# JR_main.net
KiCad netlist of a schematic drawn in Altium Designer
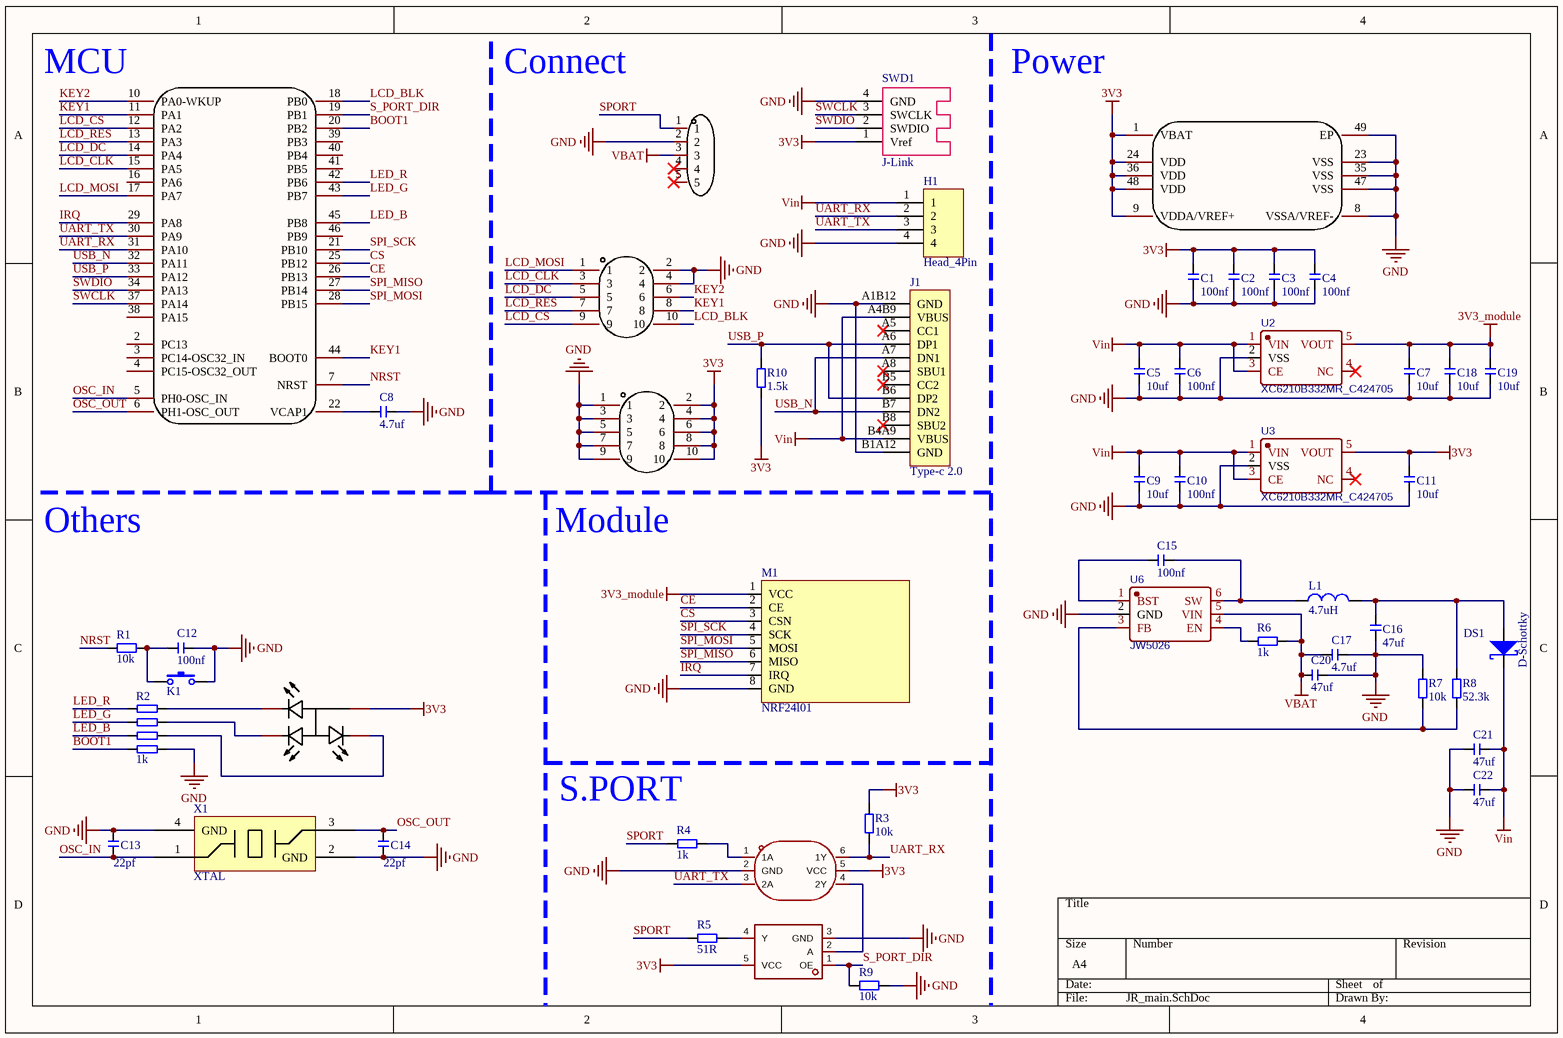
[diagram p0: JR_main.SchDoc]

(export (version "E")
  (design (tool "Eeschema 10.0.6"))
  (components
    (comp (ref "C1")
      (value "100nf")
      (footprint "C0603")
      (description "无极电容")
      (libsource (lib "Robocon_V3.0") (part "CAP"))
    )
    (comp (ref "C2")
      (value "100nf")
      (footprint "C0603")
      (description "无极电容")
      (libsource (lib "Robocon_V3.0") (part "CAP"))
    )
    (comp (ref "C3")
      (value "100nf")
      (footprint "C0603")
      (description "无极电容")
      (libsource (lib "Robocon_V3.0") (part "CAP"))
    )
    (comp (ref "C4")
      (value "100nf")
      (footprint "C0603")
      (description "无极电容")
      (libsource (lib "Robocon_V3.0") (part "CAP"))
    )
    (comp (ref "C5")
      (value "10uf")
      (footprint "C0603")
      (description "无极电容")
      (libsource (lib "Robocon_V3.0") (part "CAP"))
    )
    (comp (ref "C6")
      (value "100nf")
      (footprint "C0603")
      (description "无极电容")
      (libsource (lib "Robocon_V3.0") (part "CAP"))
    )
    (comp (ref "C7")
      (value "10uf")
      (footprint "C0603")
      (description "无极电容")
      (libsource (lib "Robocon_V3.0") (part "CAP"))
    )
    (comp (ref "C8")
      (value "4.7uf")
      (footprint "C0603")
      (description "无极电容")
      (libsource (lib "Robocon_V3.0") (part "CAP"))
    )
    (comp (ref "C9")
      (value "10uf")
      (footprint "C0603")
      (description "无极电容")
      (libsource (lib "Robocon_V3.0") (part "CAP"))
    )
    (comp (ref "C10")
      (value "100nf")
      (footprint "C0603")
      (description "无极电容")
      (libsource (lib "Robocon_V3.0") (part "CAP"))
    )
    (comp (ref "C11")
      (value "10uf")
      (footprint "C0603")
      (description "无极电容")
      (libsource (lib "Robocon_V3.0") (part "CAP"))
    )
    (comp (ref "C12")
      (value "100nf")
      (footprint "C0603")
      (description "无极电容")
      (libsource (lib "Robocon_V3.0") (part "CAP"))
    )
    (comp (ref "C13")
      (value "22pf")
      (footprint "C0603")
      (description "无极电容")
      (libsource (lib "Robocon_V3.0") (part "CAP"))
    )
    (comp (ref "C14")
      (value "22pf")
      (footprint "C0603")
      (description "无极电容")
      (libsource (lib "Robocon_V3.0") (part "CAP"))
    )
    (comp (ref "C15")
      (value "100nf")
      (footprint "C0603")
      (description "无极电容")
      (libsource (lib "Robocon_V3.0") (part "CAP"))
    )
    (comp (ref "C16")
      (value "47uf")
      (footprint "C0603")
      (description "无极电容")
      (libsource (lib "Robocon_V3.0") (part "CAP"))
    )
    (comp (ref "C17")
      (value "4.7uf")
      (footprint "C0603")
      (description "无极电容")
      (libsource (lib "Robocon_V3.0") (part "CAP"))
    )
    (comp (ref "C18")
      (value "10uf")
      (footprint "C0603")
      (description "无极电容")
      (libsource (lib "Robocon_V3.0") (part "CAP"))
    )
    (comp (ref "C19")
      (value "10uf")
      (footprint "C0603")
      (description "无极电容")
      (libsource (lib "Robocon_V3.0") (part "CAP"))
    )
    (comp (ref "C20")
      (value "47uf")
      (footprint "C1206")
      (description "无极电容")
      (libsource (lib "Robocon_V3.0") (part "CAP"))
    )
    (comp (ref "C21")
      (value "47uf")
      (footprint "C1206")
      (description "无极电容")
      (libsource (lib "Robocon_V3.0") (part "CAP"))
    )
    (comp (ref "C22")
      (value "47uf")
      (footprint "C1206")
      (description "无极电容")
      (libsource (lib "Robocon_V3.0") (part "CAP"))
    )
    (comp (ref "CN1")
      (value "B2541BW-5P")
      (footprint "CONN-TH_B2541BW-5P")
      (fields (field (name "MANUFACTURER") "CJT(长江连接器)"))
      (libsource (lib "altium-import") (part "root_0_B2541BW-5P_"))
    )
    (comp (ref "DS1")
      (value "D-Schottky")
      (footprint "SMA")
      (description "肖特基二极管")
      (libsource (lib "Robocon_V3.0") (part "Diode-Schottky"))
    )
    (comp (ref "H1")
      (value "Head_4Pin")
      (footprint "1.27排针_4PIN")
      (libsource (lib "Connector&Key") (part "Head_4Pin"))
    )
    (comp (ref "J1")
      (value "Type-c 2.0")
      (footprint "TYPE-C16PIN")
      (description "Type-c座子")
      (libsource (lib "Robocon_V3.0") (part "Type-c 2.0"))
    )
    (comp (ref "K1")
      (value "Key-PB")
      (footprint "SW_4.2x3.2")
      (description "轻触开关")
      (libsource (lib "Robocon_V3.0") (part "Key-PB"))
    )
    (comp (ref "L1")
      (value "4.7uH")
      (footprint "L-4020")
      (description "电感")
      (libsource (lib "Robocon_V3.0") (part "Lnd"))
    )
    (comp (ref "LED1")
      (value "E6C0606RGBC3UDA")
      (footprint "LED-SMD_4P-L1.6-W1.6-TL-FD")
      (fields (field (name "MANUFACTURER") "ekinglux(亿晶源)"))
      (libsource (lib "altium-import") (part "root_0_E6C0606RGBC3UDA_"))
    )
    (comp (ref "M1")
      (value "NRF24l01")
      (footprint "NRF24l01")
      (libsource (lib "altium-import") (part "root_3_NRF24l01_"))
    )
    (comp (ref "R1")
      (value "10k")
      (footprint "R0603")
      (description "电阻")
      (libsource (lib "Robocon_V3.0") (part "RES"))
    )
    (comp (ref "R2") (value "1k") (footprint "0402*4") (libsource (lib "altium-import") (part "root_0_排阻_")))
    (comp (ref "R3")
      (value "10k")
      (footprint "RES0603")
      (description "电阻")
      (libsource (lib "LCR") (part "Res"))
    )
    (comp (ref "R4")
      (value "1k")
      (footprint "RES0603")
      (description "电阻")
      (libsource (lib "LCR") (part "Res"))
    )
    (comp (ref "R5")
      (value "51R")
      (footprint "RES0603")
      (description "电阻")
      (libsource (lib "LCR") (part "Res"))
    )
    (comp (ref "R6")
      (value "1k")
      (footprint "R0603")
      (description "电阻")
      (libsource (lib "Robocon_V3.0") (part "RES"))
    )
    (comp (ref "R7")
      (value "10k")
      (footprint "R0603")
      (description "电阻")
      (libsource (lib "Robocon_V3.0") (part "RES"))
    )
    (comp (ref "R8")
      (value "52.3k")
      (footprint "R0603")
      (description "电阻")
      (libsource (lib "Robocon_V3.0") (part "RES"))
    )
    (comp (ref "R9")
      (value "10k")
      (footprint "RES0603")
      (description "电阻")
      (libsource (lib "LCR") (part "Res"))
    )
    (comp (ref "R10")
      (value "1.5k")
      (footprint "R0603")
      (description "电阻")
      (libsource (lib "Robocon_V3.0") (part "RES"))
    )
    (comp (ref "SWD1")
      (value "J-Link")
      (footprint "1.27 排针 4p")
      (description "调试接口_SWD")
      (libsource (lib "Robocon_V3.0") (part "Comm_SWD"))
    )
    (comp (ref "U1")
      (value "STM32F401CCU6")
      (footprint "UFQFPN-48_L7.0-W7.0-P0.50-BL-EP")
      (fields (field (name "MANUFACTURER") "ST(意法半导体)"))
      (libsource (lib "altium-import") (part "root_0_STM32F401CCU6_"))
    )
    (comp (ref "U2")
      (value "XC6210B332MR_C424705")
      (footprint "SOT-25_L3.0-W1.6-P0.95-LS2.8-BL")
      (description "3.3V稳压芯片")
      (fields
        (field (name "BOM_SUPPLIER PART") "C424705")
        (field (name "BOM_MANUFACTURER PART") "XC6210B332MR")
        (field (name "CONTRIBUTOR") "LCSC")
      )
      (libsource (lib "Robocon_V3.0") (part "XC6210B332MR_C424705"))
    )
    (comp (ref "U3")
      (value "XC6210B332MR_C424705")
      (footprint "SOT-25_L3.0-W1.6-P0.95-LS2.8-BL")
      (description "3.3V稳压芯片")
      (fields
        (field (name "BOM_SUPPLIER PART") "C424705")
        (field (name "BOM_MANUFACTURER PART") "XC6210B332MR")
        (field (name "CONTRIBUTOR") "LCSC")
      )
      (libsource (lib "Robocon_V3.0") (part "XC6210B332MR_C424705"))
    )
    (comp (ref "U4")
      (value "2343U-205CNG1SNT01")
      (footprint "HDR-TH_10P-P1.27-V-F-R2-C5-S1.27-1")
      (fields (field (name "MANUFACTURER") "华宇创"))
      (libsource (lib "altium-import") (part "root_0_1.27排针 2*5P_"))
    )
    (comp (ref "U5")
      (value "2343U-205CNG1SNT01")
      (footprint "HDR-TH_10P-P1.27-V-F-R2-C5-S1.27-1")
      (fields (field (name "MANUFACTURER") "华宇创"))
      (libsource (lib "altium-import") (part "root_0_1.27排针 2*5P_"))
    )
    (comp (ref "U6")
      (value "JW5026")
      (footprint "SOT-23-6_L2.9-W1.6-P0.95-LS2.8-BR - duplicate")
      (description "小尺寸降压芯片")
      (fields (field (name "BOM_SUPPLIER PART") "C185109") (field (name "CONTRIBUTOR") "LCSC"))
      (libsource (lib "Robocon_V3.0") (part "JW5026"))
    )
    (comp (ref "U7")
      (value "SN74LVC2G04DBVR")
      (footprint "SOT-23-6")
      (description "反相器")
      (libsource (lib "IC") (part "SN74LVC2G04DBVR"))
    )
    (comp (ref "U8")
      (value "SN74LVC1G126DBVR")
      (footprint "SOT-23-5")
      (description "三态输出缓存器")
      (libsource (lib "IC") (part "SN74LVC1G126DBVR"))
    )
    (comp (ref "X1")
      (value "XTAL")
      (footprint "OSC_KH3225_4P")
      (description "无源晶振")
      (libsource (lib "Robocon_V3.0") (part "XTAL_贴片"))
    )
  )
  (nets
    (net (code "1") (name "/BOOT1") (class "Default")
      (node (ref "R2") (pin "4") (pinfunction "4_4") (pintype "passive"))
      (node (ref "U1") (pin "20") (pinfunction "PB2_20") (pintype "passive"))
    )
    (net (code "2") (name "/CE") (class "Default")
      (node (ref "M1") (pin "2") (pinfunction "CE_2") (pintype "passive"))
      (node (ref "U1") (pin "26") (pinfunction "PB13_26") (pintype "passive"))
    )
    (net (code "3") (name "/CS") (class "Default")
      (node (ref "M1") (pin "3") (pinfunction "CSN_3") (pintype "passive"))
      (node (ref "U1") (pin "25") (pinfunction "PB12_25") (pintype "passive"))
    )
    (net (code "4") (name "/IRQ") (class "Default")
      (node (ref "M1") (pin "7") (pinfunction "IRQ_7") (pintype "passive"))
      (node (ref "U1") (pin "29") (pinfunction "PA8_29") (pintype "passive"))
    )
    (net (code "5") (name "/KEY1") (class "Default")
      (node (ref "U1") (pin "11") (pinfunction "PA1_11") (pintype "passive"))
      (node (ref "U1") (pin "44") (pinfunction "BOOT0_44") (pintype "passive"))
      (node (ref "U5") (pin "8") (pinfunction "8_8") (pintype "passive"))
    )
    (net (code "6") (name "/KEY2") (class "Default")
      (node (ref "U1") (pin "10") (pinfunction "PA0-WKUP_10") (pintype "passive"))
      (node (ref "U5") (pin "6") (pinfunction "6_6") (pintype "passive"))
    )
    (net (code "7") (name "/LCD_BLK") (class "Default")
      (node (ref "U1") (pin "18") (pinfunction "PB0_18") (pintype "passive"))
      (node (ref "U5") (pin "10") (pinfunction "10_10") (pintype "passive"))
    )
    (net (code "8") (name "/LCD_CLK") (class "Default")
      (node (ref "U1") (pin "15") (pinfunction "PA5_15") (pintype "passive"))
      (node (ref "U5") (pin "3") (pinfunction "3_3") (pintype "passive"))
    )
    (net (code "9") (name "/LCD_CS") (class "Default")
      (node (ref "U1") (pin "12") (pinfunction "PA2_12") (pintype "passive"))
      (node (ref "U5") (pin "9") (pinfunction "9_9") (pintype "passive"))
    )
    (net (code "10") (name "/LCD_DC") (class "Default")
      (node (ref "U1") (pin "14") (pinfunction "PA4_14") (pintype "passive"))
      (node (ref "U5") (pin "5") (pinfunction "5_5") (pintype "passive"))
    )
    (net (code "11") (name "/LCD_MOSI") (class "Default")
      (node (ref "U1") (pin "17") (pinfunction "PA7_17") (pintype "passive"))
      (node (ref "U5") (pin "1") (pinfunction "1_1") (pintype "passive"))
    )
    (net (code "12") (name "/LCD_RES") (class "Default")
      (node (ref "U1") (pin "13") (pinfunction "PA3_13") (pintype "passive"))
      (node (ref "U5") (pin "7") (pinfunction "7_7") (pintype "passive"))
    )
    (net (code "13") (name "/LED_B") (class "Default")
      (node (ref "R2") (pin "3") (pinfunction "3_3") (pintype "passive"))
      (node (ref "U1") (pin "45") (pinfunction "PB8_45") (pintype "passive"))
    )
    (net (code "14") (name "/LED_G") (class "Default")
      (node (ref "R2") (pin "2") (pinfunction "2_2") (pintype "passive"))
      (node (ref "U1") (pin "43") (pinfunction "PB7_43") (pintype "passive"))
    )
    (net (code "15") (name "/LED_R") (class "Default")
      (node (ref "R2") (pin "1") (pinfunction "1_1") (pintype "passive"))
      (node (ref "U1") (pin "42") (pinfunction "PB6_42") (pintype "passive"))
    )
    (net (code "16") (name "/NRST") (class "Default")
      (node (ref "R1") (pin "1") (pinfunction "1_1") (pintype "passive"))
      (node (ref "U1") (pin "7") (pinfunction "NRST_7") (pintype "passive"))
    )
    (net (code "17") (name "/OSC_IN") (class "Default")
      (node (ref "C13") (pin "1") (pinfunction "1_1") (pintype "passive"))
      (node (ref "U1") (pin "5") (pinfunction "PH0-OSC_IN_5") (pintype "passive"))
      (node (ref "X1") (pin "1") (pinfunction "OSC1_1") (pintype "passive"))
    )
    (net (code "18") (name "/OSC_OUT") (class "Default")
      (node (ref "C14") (pin "2") (pinfunction "2_2") (pintype "passive"))
      (node (ref "U1") (pin "6") (pinfunction "PH1-OSC_OUT_6") (pintype "passive"))
      (node (ref "X1") (pin "3") (pinfunction "OSC2_3") (pintype "passive"))
    )
    (net (code "19") (name "/SPI_MISO") (class "Default")
      (node (ref "M1") (pin "6") (pinfunction "MISO_6") (pintype "passive"))
      (node (ref "U1") (pin "27") (pinfunction "PB14_27") (pintype "passive"))
    )
    (net (code "20") (name "/SPI_MOSI") (class "Default")
      (node (ref "M1") (pin "5") (pinfunction "MOSI_5") (pintype "passive"))
      (node (ref "U1") (pin "28") (pinfunction "PB15_28") (pintype "passive"))
    )
    (net (code "21") (name "/SPI_SCK") (class "Default")
      (node (ref "M1") (pin "4") (pinfunction "SCK_4") (pintype "passive"))
      (node (ref "U1") (pin "21") (pinfunction "PB10_21") (pintype "passive"))
    )
    (net (code "22") (name "/SPORT") (class "Default")
      (node (ref "CN1") (pin "1") (pinfunction "1_1") (pintype "passive"))
      (node (ref "R4") (pin "2") (pinfunction "2_2") (pintype "passive"))
      (node (ref "R5") (pin "2") (pinfunction "2_2") (pintype "passive"))
    )
    (net (code "23") (name "/SWCLK") (class "Default")
      (node (ref "SWD1") (pin "3") (pinfunction "SWCLK_3") (pintype "passive"))
      (node (ref "U1") (pin "37") (pinfunction "PA14_37") (pintype "passive"))
    )
    (net (code "24") (name "/SWDIO") (class "Default")
      (node (ref "SWD1") (pin "2") (pinfunction "SWDIO_2") (pintype "passive"))
      (node (ref "U1") (pin "34") (pinfunction "PA13_34") (pintype "passive"))
    )
    (net (code "25") (name "/S_PORT_DIR") (class "Default")
      (node (ref "R9") (pin "2") (pinfunction "2_2") (pintype "passive"))
      (node (ref "U1") (pin "19") (pinfunction "PB1_19") (pintype "passive"))
      (node (ref "U8") (pin "1") (pinfunction "OE_1") (pintype "passive"))
    )
    (net (code "26") (name "/UART_RX") (class "Default")
      (node (ref "H1") (pin "2") (pinfunction "2_2") (pintype "passive"))
      (node (ref "R3") (pin "1") (pinfunction "1_1") (pintype "passive"))
      (node (ref "U1") (pin "31") (pinfunction "PA10_31") (pintype "passive"))
      (node (ref "U7") (pin "6") (pinfunction "1Y_6") (pintype "passive"))
    )
    (net (code "27") (name "/UART_TX") (class "Default")
      (node (ref "H1") (pin "3") (pinfunction "3_3") (pintype "passive"))
      (node (ref "U1") (pin "30") (pinfunction "PA9_30") (pintype "passive"))
      (node (ref "U7") (pin "3") (pinfunction "2A_3") (pintype "passive"))
    )
    (net (code "28") (name "/USB_N") (class "Default")
      (node (ref "J1") (pin "A7") (pinfunction "DN1_A7") (pintype "passive"))
      (node (ref "J1") (pin "B7") (pinfunction "DN2_B7") (pintype "passive"))
      (node (ref "U1") (pin "32") (pinfunction "PA11_32") (pintype "passive"))
    )
    (net (code "29") (name "/USB_P") (class "Default")
      (node (ref "J1") (pin "A6") (pinfunction "DP1_A6") (pintype "passive"))
      (node (ref "J1") (pin "B6") (pinfunction "DP2_B6") (pintype "passive"))
      (node (ref "R10") (pin "2") (pinfunction "2_2") (pintype "passive"))
      (node (ref "U1") (pin "33") (pinfunction "PA12_33") (pintype "passive"))
    )
    (net (code "30") (name "3V3") (class "Default")
      (node (ref "C1") (pin "2") (pinfunction "2_2") (pintype "passive"))
      (node (ref "C11") (pin "2") (pinfunction "2_2") (pintype "passive"))
      (node (ref "C2") (pin "2") (pinfunction "2_2") (pintype "passive"))
      (node (ref "C3") (pin "2") (pinfunction "2_2") (pintype "passive"))
      (node (ref "C4") (pin "2") (pinfunction "2_2") (pintype "passive"))
      (node (ref "LED1") (pin "2") (pinfunction "+_2") (pintype "passive"))
      (node (ref "R10") (pin "1") (pinfunction "1_1") (pintype "passive"))
      (node (ref "R3") (pin "2") (pinfunction "2_2") (pintype "passive"))
      (node (ref "SWD1") (pin "1") (pinfunction "Vref_1") (pintype "passive"))
      (node (ref "U1") (pin "1") (pinfunction "VBAT_1") (pintype "passive"))
      (node (ref "U1") (pin "24") (pinfunction "VDD_24") (pintype "passive"))
      (node (ref "U1") (pin "36") (pinfunction "VDD_36") (pintype "passive"))
      (node (ref "U1") (pin "48") (pinfunction "VDD_48") (pintype "passive"))
      (node (ref "U1") (pin "9") (pinfunction "VDDA/VREF+_9") (pintype "passive"))
      (node (ref "U3") (pin "5") (pinfunction "VOUT_5") (pintype "passive"))
      (node (ref "U4") (pin "10") (pinfunction "10_10") (pintype "passive"))
      (node (ref "U4") (pin "2") (pinfunction "2_2") (pintype "passive"))
      (node (ref "U4") (pin "4") (pinfunction "4_4") (pintype "passive"))
      (node (ref "U4") (pin "6") (pinfunction "6_6") (pintype "passive"))
      (node (ref "U4") (pin "8") (pinfunction "8_8") (pintype "passive"))
      (node (ref "U7") (pin "5") (pinfunction "VCC_5") (pintype "passive"))
      (node (ref "U8") (pin "5") (pinfunction "VCC_5") (pintype "passive"))
    )
    (net (code "31") (name "3V3_module") (class "Default")
      (node (ref "C18") (pin "2") (pinfunction "2_2") (pintype "passive"))
      (node (ref "C19") (pin "2") (pinfunction "2_2") (pintype "passive"))
      (node (ref "C7") (pin "2") (pinfunction "2_2") (pintype "passive"))
      (node (ref "M1") (pin "1") (pinfunction "VCC_1") (pintype "passive"))
      (node (ref "U2") (pin "5") (pinfunction "VOUT_5") (pintype "passive"))
    )
    (net (code "32") (name "GND") (class "Default")
      (node (ref "C1") (pin "1") (pinfunction "1_1") (pintype "passive"))
      (node (ref "C10") (pin "1") (pinfunction "1_1") (pintype "passive"))
      (node (ref "C11") (pin "1") (pinfunction "1_1") (pintype "passive"))
      (node (ref "C12") (pin "1") (pinfunction "1_1") (pintype "passive"))
      (node (ref "C13") (pin "2") (pinfunction "2_2") (pintype "passive"))
      (node (ref "C14") (pin "1") (pinfunction "1_1") (pintype "passive"))
      (node (ref "C16") (pin "1") (pinfunction "1_1") (pintype "passive"))
      (node (ref "C17") (pin "1") (pinfunction "1_1") (pintype "passive"))
      (node (ref "C18") (pin "1") (pinfunction "1_1") (pintype "passive"))
      (node (ref "C19") (pin "1") (pinfunction "1_1") (pintype "passive"))
      (node (ref "C2") (pin "1") (pinfunction "1_1") (pintype "passive"))
      (node (ref "C20") (pin "1") (pinfunction "1_1") (pintype "passive"))
      (node (ref "C21") (pin "2") (pinfunction "2_2") (pintype "passive"))
      (node (ref "C22") (pin "2") (pinfunction "2_2") (pintype "passive"))
      (node (ref "C3") (pin "1") (pinfunction "1_1") (pintype "passive"))
      (node (ref "C4") (pin "1") (pinfunction "1_1") (pintype "passive"))
      (node (ref "C5") (pin "2") (pinfunction "2_2") (pintype "passive"))
      (node (ref "C6") (pin "1") (pinfunction "1_1") (pintype "passive"))
      (node (ref "C7") (pin "1") (pinfunction "1_1") (pintype "passive"))
      (node (ref "C8") (pin "2") (pinfunction "2_2") (pintype "passive"))
      (node (ref "C9") (pin "2") (pinfunction "2_2") (pintype "passive"))
      (node (ref "CN1") (pin "2") (pinfunction "2_2") (pintype "passive"))
      (node (ref "H1") (pin "4") (pinfunction "4_4") (pintype "passive"))
      (node (ref "J1") (pin "A1B12") (pinfunction "GND_A1B12") (pintype "passive"))
      (node (ref "J1") (pin "B1A12") (pinfunction "GND_B1A12") (pintype "passive"))
      (node (ref "K1") (pin "2") (pinfunction "2_2") (pintype "passive"))
      (node (ref "M1") (pin "8") (pinfunction "GND_8") (pintype "passive"))
      (node (ref "R2") (pin "5") (pinfunction "5_5") (pintype "passive"))
      (node (ref "R7") (pin "2") (pinfunction "2_2") (pintype "passive"))
      (node (ref "R9") (pin "1") (pinfunction "1_1") (pintype "passive"))
      (node (ref "SWD1") (pin "4") (pinfunction "GND_4") (pintype "passive"))
      (node (ref "U1") (pin "23") (pinfunction "VSS_23") (pintype "passive"))
      (node (ref "U1") (pin "35") (pinfunction "VSS_35") (pintype "passive"))
      (node (ref "U1") (pin "47") (pinfunction "VSS_47") (pintype "passive"))
      (node (ref "U1") (pin "49") (pinfunction "EP_49") (pintype "passive"))
      (node (ref "U1") (pin "8") (pinfunction "VSSA/VREF-_8") (pintype "passive"))
      (node (ref "U2") (pin "2") (pinfunction "VSS_2") (pintype "passive"))
      (node (ref "U3") (pin "2") (pinfunction "VSS_2") (pintype "passive"))
      (node (ref "U4") (pin "1") (pinfunction "1_1") (pintype "passive"))
      (node (ref "U4") (pin "3") (pinfunction "3_3") (pintype "passive"))
      (node (ref "U4") (pin "5") (pinfunction "5_5") (pintype "passive"))
      (node (ref "U4") (pin "7") (pinfunction "7_7") (pintype "passive"))
      (node (ref "U4") (pin "9") (pinfunction "9_9") (pintype "passive"))
      (node (ref "U5") (pin "2") (pinfunction "2_2") (pintype "passive"))
      (node (ref "U5") (pin "4") (pinfunction "4_4") (pintype "passive"))
      (node (ref "U6") (pin "2") (pinfunction "GND_2") (pintype "passive"))
      (node (ref "U7") (pin "2") (pinfunction "GND_2") (pintype "passive"))
      (node (ref "U8") (pin "3") (pinfunction "GND_3") (pintype "passive"))
      (node (ref "X1") (pin "2") (pinfunction "GND_2") (pintype "passive"))
      (node (ref "X1") (pin "4") (pinfunction "GND_4") (pintype "passive"))
    )
    (net (code "33") (name "Net-(C12-Pad2)") (class "Default")
      (node (ref "C12") (pin "2") (pinfunction "2_2") (pintype "passive"))
      (node (ref "K1") (pin "1") (pinfunction "1_1") (pintype "passive"))
      (node (ref "R1") (pin "2") (pinfunction "2_2") (pintype "passive"))
    )
    (net (code "34") (name "Net-(C16-Pad2)") (class "Default")
      (node (ref "C16") (pin "2") (pinfunction "2_2") (pintype "passive"))
      (node (ref "DS1") (pin "1") (pinfunction "1_1") (pintype "power_in"))
      (node (ref "L1") (pin "2") (pinfunction "2_2") (pintype "passive"))
      (node (ref "R8") (pin "2") (pinfunction "2_2") (pintype "passive"))
    )
    (net (code "35") (name "Net-(LED1---Pad1)") (class "Default")
      (node (ref "LED1") (pin "1") (pinfunction "-_1") (pintype "passive"))
      (node (ref "R2") (pin "8") (pinfunction "8_8") (pintype "passive"))
    )
    (net (code "36") (name "Net-(LED1---Pad3)") (class "Default")
      (node (ref "LED1") (pin "3") (pinfunction "-_3") (pintype "passive"))
      (node (ref "R2") (pin "7") (pinfunction "7_7") (pintype "passive"))
    )
    (net (code "37") (name "Net-(LED1---Pad4)") (class "Default")
      (node (ref "LED1") (pin "4") (pinfunction "-_4") (pintype "passive"))
      (node (ref "R2") (pin "6") (pinfunction "6_6") (pintype "passive"))
    )
    (net (code "38") (name "Net-(U1A-VCAP1)") (class "Default")
      (node (ref "C8") (pin "1") (pinfunction "1_1") (pintype "passive"))
      (node (ref "U1") (pin "22") (pinfunction "VCAP1_22") (pintype "passive"))
    )
    (net (code "39") (name "Net-(U6-BST)") (class "Default")
      (node (ref "C15") (pin "1") (pinfunction "1_1") (pintype "passive"))
      (node (ref "U6") (pin "1") (pinfunction "BST_1") (pintype "passive"))
    )
    (net (code "40") (name "Net-(U6-EN)") (class "Default")
      (node (ref "R6") (pin "1") (pinfunction "1_1") (pintype "passive"))
      (node (ref "U6") (pin "4") (pinfunction "EN_4") (pintype "passive"))
    )
    (net (code "41") (name "Net-(U6-FB)") (class "Default")
      (node (ref "R7") (pin "1") (pinfunction "1_1") (pintype "passive"))
      (node (ref "R8") (pin "1") (pinfunction "1_1") (pintype "passive"))
      (node (ref "U6") (pin "3") (pinfunction "FB_3") (pintype "passive"))
    )
    (net (code "42") (name "Net-(U6-SW)") (class "Default")
      (node (ref "C15") (pin "2") (pinfunction "2_2") (pintype "passive"))
      (node (ref "L1") (pin "1") (pinfunction "1_1") (pintype "passive"))
      (node (ref "U6") (pin "6") (pinfunction "SW_6") (pintype "passive"))
    )
    (net (code "43") (name "Net-(U7-1A)") (class "Default")
      (node (ref "R4") (pin "1") (pinfunction "1_1") (pintype "passive"))
      (node (ref "U7") (pin "1") (pinfunction "1A_1") (pintype "passive"))
    )
    (net (code "44") (name "Net-(U7-2Y)") (class "Default")
      (node (ref "U7") (pin "4") (pinfunction "2Y_4") (pintype "passive"))
      (node (ref "U8") (pin "2") (pinfunction "A_2") (pintype "passive"))
    )
    (net (code "45") (name "Net-(U8-Y)") (class "Default")
      (node (ref "R5") (pin "1") (pinfunction "1_1") (pintype "passive"))
      (node (ref "U8") (pin "4") (pinfunction "Y_4") (pintype "passive"))
    )
    (net (code "46") (name "VBAT") (class "Default")
      (node (ref "C17") (pin "2") (pinfunction "2_2") (pintype "passive"))
      (node (ref "C20") (pin "2") (pinfunction "2_2") (pintype "passive"))
      (node (ref "CN1") (pin "3") (pinfunction "3_3") (pintype "passive"))
      (node (ref "R6") (pin "2") (pinfunction "2_2") (pintype "passive"))
      (node (ref "U6") (pin "5") (pinfunction "VIN_5") (pintype "passive"))
    )
    (net (code "47") (name "Vin") (class "Default")
      (node (ref "C10") (pin "2") (pinfunction "2_2") (pintype "passive"))
      (node (ref "C21") (pin "1") (pinfunction "1_1") (pintype "passive"))
      (node (ref "C22") (pin "1") (pinfunction "1_1") (pintype "passive"))
      (node (ref "C5") (pin "1") (pinfunction "1_1") (pintype "passive"))
      (node (ref "C6") (pin "2") (pinfunction "2_2") (pintype "passive"))
      (node (ref "C9") (pin "1") (pinfunction "1_1") (pintype "passive"))
      (node (ref "DS1") (pin "2") (pinfunction "2_2") (pintype "power_in"))
      (node (ref "H1") (pin "1") (pinfunction "1_1") (pintype "passive"))
      (node (ref "J1") (pin "A4B9") (pinfunction "VBUS_A4B9") (pintype "passive"))
      (node (ref "J1") (pin "B4A9") (pinfunction "VBUS_B4A9") (pintype "passive"))
      (node (ref "U2") (pin "1") (pinfunction "VIN_1") (pintype "passive"))
      (node (ref "U2") (pin "3") (pinfunction "CE_3") (pintype "passive"))
      (node (ref "U3") (pin "1") (pinfunction "VIN_1") (pintype "passive"))
      (node (ref "U3") (pin "3") (pinfunction "CE_3") (pintype "passive"))
    )
    (net (code "48") (name "unconnected-(CN1-Pad4)") (class "Default")
      (node (ref "CN1") (pin "4") (pinfunction "4_4") (pintype "passive+no_connect"))
    )
    (net (code "49") (name "unconnected-(CN1-Pad5)") (class "Default")
      (node (ref "CN1") (pin "5") (pinfunction "5_5") (pintype "passive+no_connect"))
    )
    (net (code "50") (name "unconnected-(J1-CC1-PadA5)") (class "Default")
      (node (ref "J1") (pin "A5") (pinfunction "CC1_A5") (pintype "passive+no_connect"))
    )
    (net (code "51") (name "unconnected-(J1-CC2-PadB5)") (class "Default")
      (node (ref "J1") (pin "B5") (pinfunction "CC2_B5") (pintype "passive+no_connect"))
    )
    (net (code "52") (name "unconnected-(J1-SBU1-PadA8)") (class "Default")
      (node (ref "J1") (pin "A8") (pinfunction "SBU1_A8") (pintype "passive+no_connect"))
    )
    (net (code "53") (name "unconnected-(J1-SBU2-PadB8)") (class "Default")
      (node (ref "J1") (pin "B8") (pinfunction "SBU2_B8") (pintype "passive+no_connect"))
    )
    (net (code "54") (name "unconnected-(U1A-PA6-Pad16)") (class "Default")
      (node (ref "U1") (pin "16") (pinfunction "PA6_16") (pintype "passive"))
    )
    (net (code "55") (name "unconnected-(U1A-PA15-Pad38)") (class "Default")
      (node (ref "U1") (pin "38") (pinfunction "PA15_38") (pintype "passive"))
    )
    (net (code "56") (name "unconnected-(U1A-PB3-Pad39)") (class "Default")
      (node (ref "U1") (pin "39") (pinfunction "PB3_39") (pintype "passive"))
    )
    (net (code "57") (name "unconnected-(U1A-PB4-Pad40)") (class "Default")
      (node (ref "U1") (pin "40") (pinfunction "PB4_40") (pintype "passive"))
    )
    (net (code "58") (name "unconnected-(U1A-PB5-Pad41)") (class "Default")
      (node (ref "U1") (pin "41") (pinfunction "PB5_41") (pintype "passive"))
    )
    (net (code "59") (name "unconnected-(U1A-PB9-Pad46)") (class "Default")
      (node (ref "U1") (pin "46") (pinfunction "PB9_46") (pintype "passive"))
    )
    (net (code "60") (name "unconnected-(U1A-PC13-Pad2)") (class "Default")
      (node (ref "U1") (pin "2") (pinfunction "PC13_2") (pintype "passive"))
    )
    (net (code "61") (name "unconnected-(U1A-PC14-OSC32_IN-Pad3)") (class "Default")
      (node (ref "U1") (pin "3") (pinfunction "PC14-OSC32_IN_3") (pintype "passive"))
    )
    (net (code "62") (name "unconnected-(U1A-PC15-OSC32_OUT-Pad4)") (class "Default")
      (node (ref "U1") (pin "4") (pinfunction "PC15-OSC32_OUT_4") (pintype "passive"))
    )
    (net (code "63") (name "unconnected-(U2-NC-Pad4)") (class "Default")
      (node (ref "U2") (pin "4") (pinfunction "NC_4") (pintype "passive+no_connect"))
    )
    (net (code "64") (name "unconnected-(U3-NC-Pad4)") (class "Default")
      (node (ref "U3") (pin "4") (pinfunction "NC_4") (pintype "passive+no_connect"))
    )
  )
)
